# 01_JUMPER.net
KiCad netlist of a schematic drawn in Altium Designer
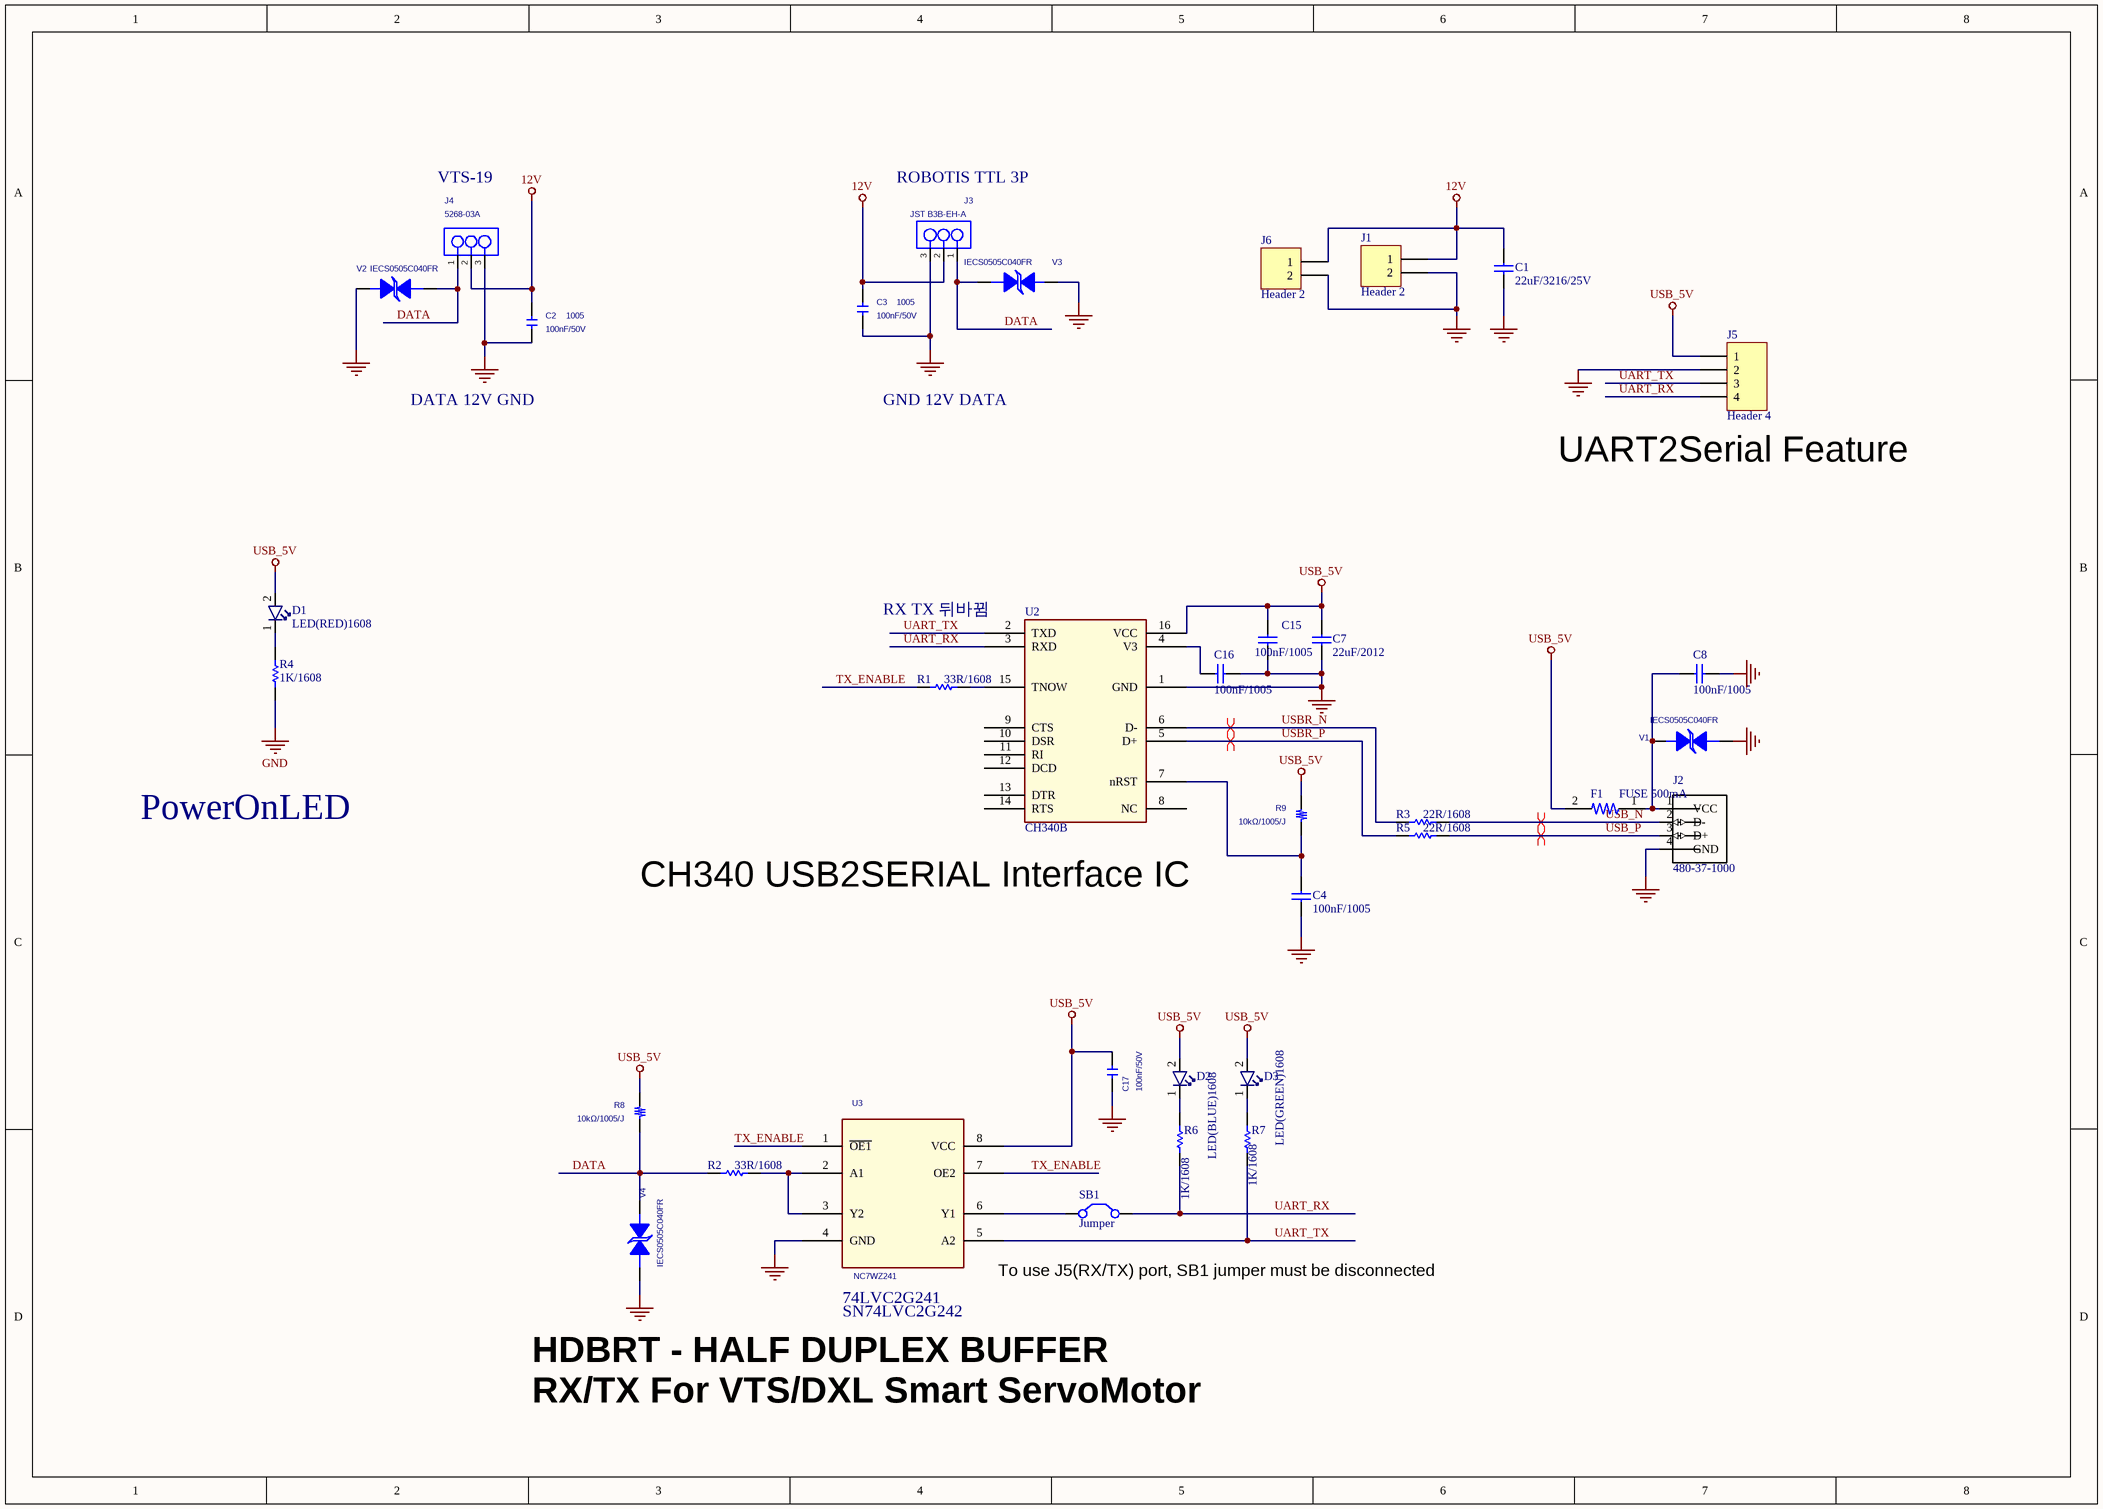
[diagram p0: 01_JUMPER.SchDoc]

(export (version "E")
  (design (tool "Eeschema 10.0.6"))
  (components
    (comp (ref "C1")
      (value "22uF/3216/25V")
      (footprint "C3216-LJS")
      (description "Capacitor, NP0, ±0.1pF")
      (libsource (lib "RLC") (part "CAP_0402"))
    )
    (comp (ref "C2")
      (value "100nF/50V")
      (footprint "CAPC1608X06L")
      (fields (field (name "SIZE") "1005") (field (name "Comment") "CAP-CHIP-1005"))
      (libsource (lib "*") (part "CAP-CHIP-1005"))
    )
    (comp (ref "C3")
      (value "100nF/50V")
      (footprint "CAPC1608X06L")
      (fields (field (name "SIZE") "1005") (field (name "Comment") "CAP-CHIP-1005"))
      (libsource (lib "*") (part "CAP-CHIP-1005"))
    )
    (comp (ref "C4")
      (value "100nF/1005")
      (footprint "CAPC1608X06L")
      (description "Capacitor, NP0, ±0.1pF")
      (libsource (lib "RLC") (part "CAP_0402"))
    )
    (comp (ref "C7")
      (value "22uF/2012")
      (footprint "CAPC2012X00L")
      (description "Capacitor, NP0, ±0.1pF")
      (libsource (lib "RLC") (part "CAP_0402"))
    )
    (comp (ref "C8")
      (value "100nF/1005")
      (footprint "CAPC1608X06L")
      (description "Capacitor, NP0, ±0.1pF")
      (libsource (lib "RLC") (part "CAP_0402"))
    )
    (comp (ref "C15")
      (value "100nF/1005")
      (footprint "CAPC1608X06L")
      (description "Capacitor, NP0, ±0.1pF")
      (libsource (lib "RLC") (part "CAP_0402"))
    )
    (comp (ref "C16")
      (value "100nF/1005")
      (footprint "CAPC1608X06L")
      (description "Capacitor, NP0, ±0.1pF")
      (libsource (lib "RLC") (part "CAP_0402"))
    )
    (comp (ref "C17")
      (value "100nF/50V")
      (footprint "CAPC1608X06L")
      (fields (field (name "Comment") "CAP-CHIP-1005"))
      (libsource (lib "*") (part "CAP-CHIP-1005"))
    )
    (comp (ref "D1")
      (value "LED(RED)1608")
      (footprint "LED_0603_G")
      (description "LED SMARTLED GREEN 570NM 0603")
      (libsource (lib "RLC") (part "D{colon}LED"))
    )
    (comp (ref "D2")
      (value "LED(BLUE)1608")
      (footprint "LED_0603_G")
      (description "LED SMARTLED GREEN 570NM 0603")
      (libsource (lib "RLC") (part "D{colon}LED"))
    )
    (comp (ref "D3")
      (value "LED(GREEN)1608")
      (footprint "LED_0603_G")
      (description "LED SMARTLED GREEN 570NM 0603")
      (libsource (lib "RLC") (part "D{colon}LED"))
    )
    (comp (ref "F1")
      (value "FUSE 500mA")
      (footprint "FUSE1812")
      (description "1206 SMT PPTC ¦ 0.50 Ih ¦ 24V")
      (fields (field (name "MP") "0ZCJ0050AF2E") (field (name "MF") "Bel Fuse"))
      (libsource (lib "VTC-1_v1.2") (part "0ZCJ0050AF2E"))
    )
    (comp (ref "J1")
      (value "Header 2")
      (footprint "HDR1X2")
      (description "Header, 2-Pin")
      (fields (field (name "PUBLISHER") "Altium Limited"))
      (libsource (lib "Miscellaneous Connectors") (part "Header 2"))
    )
    (comp (ref "J2")
      (value "480-37-1000")
      (footprint "MOLEX_480-37-1000")
      (description "USB-A _USB TYPE-A_ USB 2.0 Plug Connector 4 Position Surface Mount, Right Angle; Through Hole")
      (fields (field (name "MP") "48037-1000") (field (name "MF") "Molex"))
      (libsource (lib "Connector") (part "480-37-1000"))
    )
    (comp (ref "J3")
      (value "JST B3B-EH-A")
      (footprint "JST_B3B-EH-A")
      (libsource (lib "*") (part "5268-03A"))
    )
    (comp (ref "J4") (value "5268-03A") (footprint "5267-03") (libsource (lib "*") (part "5268-03A")))
    (comp (ref "J5")
      (value "Header 4")
      (footprint "5267-04A-2.5P")
      (description "Header, 4-Pin")
      (fields (field (name "PUBLISHER") "Altium Limited"))
      (libsource (lib "Miscellaneous Connectors") (part "Header 4"))
    )
    (comp (ref "J6")
      (value "Header 2")
      (footprint "BLOCK-5.08MMX2P_NO_SILK")
      (description "Header, 2-Pin")
      (fields (field (name "PUBLISHER") "Altium Limited"))
      (libsource (lib "Miscellaneous Connectors") (part "Header 2"))
    )
    (comp (ref "R1")
      (value "33R/1608")
      (footprint "RESC1608X06L")
      (description "Not mounted")
      (libsource (lib "RLC") (part "RES_0603"))
    )
    (comp (ref "R2")
      (value "33R/1608")
      (footprint "RESC1608X06L")
      (description "Not mounted")
      (libsource (lib "RLC") (part "RES_0603"))
    )
    (comp (ref "R3")
      (value "22R/1608")
      (footprint "RESC1608X06L")
      (description "Not mounted")
      (libsource (lib "RLC") (part "RES_0603"))
    )
    (comp (ref "R4")
      (value "1K/1608")
      (footprint "RESC1608X06L")
      (description "Not mounted")
      (libsource (lib "RLC") (part "RES_0603"))
    )
    (comp (ref "R5")
      (value "22R/1608")
      (footprint "RESC1608X06L")
      (description "Not mounted")
      (libsource (lib "RLC") (part "RES_0603"))
    )
    (comp (ref "R6")
      (value "1K/1608")
      (footprint "RESC1608X06L")
      (description "Not mounted")
      (libsource (lib "RLC") (part "RES_0603"))
    )
    (comp (ref "R7")
      (value "1K/1608")
      (footprint "RESC1608X06L")
      (description "Not mounted")
      (libsource (lib "RLC") (part "RES_0603"))
    )
    (comp (ref "R8")
      (value "10kΩ/1005/J")
      (footprint "RESC1608X06L")
      (fields (field (name "Comment") "RES-CHIP-1005"))
      (libsource (lib "*") (part "RES-CHIP-1005"))
    )
    (comp (ref "R9")
      (value "10kΩ/1005/J")
      (footprint "RESC1608X06L")
      (fields (field (name "Comment") "RES-CHIP-1005"))
      (libsource (lib "*") (part "RES-CHIP-1005"))
    )
    (comp (ref "SB1")
      (value "Jumper")
      (footprint "Solderbridge_Shorted")
      (description "Jumper Wire")
      (fields (field (name "PUBLISHER") "Altium Limited"))
      (libsource (lib "Miscellaneous Devices") (part "Jumper"))
    )
    (comp (ref "U2") (value "CH340B") (footprint "SOIC16P-50MIL") (libsource (lib "IC") (part "CH340B")))
    (comp (ref "U3")
      (value "NC7WZ241")
      (footprint "MO-187_0.5_2.0X3.1")
      (libsource (lib "*") (part "NC7WZ241"))
    )
    (comp (ref "V1")
      (value "IECS0505C040FR")
      (footprint "RESC1608X06L")
      (libsource (lib "*") (part "DIODE TVS_1"))
    )
    (comp (ref "V2")
      (value "IECS0505C040FR")
      (footprint "RESC1608X06L")
      (libsource (lib "*") (part "DIODE TVS_1"))
    )
    (comp (ref "V3")
      (value "IECS0505C040FR")
      (footprint "RESC1608X06L")
      (libsource (lib "*") (part "DIODE TVS_1"))
    )
    (comp (ref "V4")
      (value "IECS0505C040FR")
      (footprint "RESC1608X06L")
      (libsource (lib "*") (part "DIODE TVS_1"))
    )
  )
  (nets
    (net (code "1") (name "/DATA") (class "Default")
      (node (ref "J3") (pin "1") (pinfunction "1_1") (pintype "passive"))
      (node (ref "J4") (pin "1") (pinfunction "1_1") (pintype "passive"))
      (node (ref "R2") (pin "2") (pinfunction "2_2") (pintype "passive"))
      (node (ref "R8") (pin "1") (pinfunction "1_1") (pintype "passive"))
      (node (ref "V2") (pin "1") (pinfunction "ANODE_1") (pintype "passive"))
      (node (ref "V3") (pin "1") (pinfunction "ANODE_1") (pintype "passive"))
      (node (ref "V4") (pin "2") (pinfunction "CATHODE_2") (pintype "passive"))
    )
    (net (code "2") (name "/TX_ENABLE") (class "Default")
      (node (ref "R1") (pin "2") (pinfunction "2_2") (pintype "passive"))
      (node (ref "U3") (pin "1") (pinfunction "~{OE1}_1") (pintype "passive"))
      (node (ref "U3") (pin "7") (pinfunction "OE2_7") (pintype "passive"))
    )
    (net (code "3") (name "/UART_RX") (class "Default")
      (node (ref "J5") (pin "4") (pinfunction "4_4") (pintype "passive"))
      (node (ref "R6") (pin "1") (pinfunction "1_1") (pintype "passive"))
      (node (ref "SB1") (pin "2") (pinfunction "C2_2") (pintype "passive"))
      (node (ref "U2") (pin "3") (pinfunction "RXD_3") (pintype "passive"))
    )
    (net (code "4") (name "/UART_TX") (class "Default")
      (node (ref "J5") (pin "3") (pinfunction "3_3") (pintype "passive"))
      (node (ref "R7") (pin "1") (pinfunction "1_1") (pintype "passive"))
      (node (ref "U2") (pin "2") (pinfunction "TXD_2") (pintype "passive"))
      (node (ref "U3") (pin "5") (pinfunction "A2_5") (pintype "passive"))
    )
    (net (code "5") (name "/USBR_N") (class "Default")
      (node (ref "R3") (pin "2") (pinfunction "2_2") (pintype "passive"))
      (node (ref "U2") (pin "6") (pinfunction "D-_6") (pintype "passive"))
    )
    (net (code "6") (name "/USBR_P") (class "Default")
      (node (ref "R5") (pin "2") (pinfunction "2_2") (pintype "passive"))
      (node (ref "U2") (pin "5") (pinfunction "D+_5") (pintype "passive"))
    )
    (net (code "7") (name "/USB_N") (class "Default")
      (node (ref "J2") (pin "2") (pinfunction "D-_2") (pintype "bidirectional"))
      (node (ref "R3") (pin "1") (pinfunction "1_1") (pintype "passive"))
    )
    (net (code "8") (name "/USB_P") (class "Default")
      (node (ref "J2") (pin "3") (pinfunction "D+_3") (pintype "bidirectional"))
      (node (ref "R5") (pin "1") (pinfunction "1_1") (pintype "passive"))
    )
    (net (code "9") (name "12V") (class "Default")
      (node (ref "C1") (pin "1") (pinfunction "1_1") (pintype "passive"))
      (node (ref "C2") (pin "2") (pinfunction "2_2") (pintype "passive"))
      (node (ref "C3") (pin "2") (pinfunction "2_2") (pintype "passive"))
      (node (ref "J1") (pin "1") (pinfunction "1_1") (pintype "passive"))
      (node (ref "J3") (pin "2") (pinfunction "2_2") (pintype "passive"))
      (node (ref "J4") (pin "2") (pinfunction "2_2") (pintype "passive"))
      (node (ref "J6") (pin "1") (pinfunction "1_1") (pintype "passive"))
    )
    (net (code "10") (name "GND") (class "Default")
      (node (ref "C1") (pin "2") (pinfunction "2_2") (pintype "passive"))
      (node (ref "C15") (pin "2") (pinfunction "2_2") (pintype "passive"))
      (node (ref "C16") (pin "2") (pinfunction "2_2") (pintype "passive"))
      (node (ref "C17") (pin "1") (pinfunction "1_1") (pintype "passive"))
      (node (ref "C2") (pin "1") (pinfunction "1_1") (pintype "passive"))
      (node (ref "C3") (pin "1") (pinfunction "1_1") (pintype "passive"))
      (node (ref "C4") (pin "1") (pinfunction "1_1") (pintype "passive"))
      (node (ref "C7") (pin "2") (pinfunction "2_2") (pintype "passive"))
      (node (ref "C8") (pin "2") (pinfunction "2_2") (pintype "passive"))
      (node (ref "J1") (pin "2") (pinfunction "2_2") (pintype "passive"))
      (node (ref "J2") (pin "4") (pinfunction "GND_4") (pintype "power_in"))
      (node (ref "J3") (pin "3") (pinfunction "3_3") (pintype "passive"))
      (node (ref "J4") (pin "3") (pinfunction "3_3") (pintype "passive"))
      (node (ref "J5") (pin "2") (pinfunction "2_2") (pintype "passive"))
      (node (ref "J6") (pin "2") (pinfunction "2_2") (pintype "passive"))
      (node (ref "R4") (pin "1") (pinfunction "1_1") (pintype "passive"))
      (node (ref "U2") (pin "1") (pinfunction "GND_1") (pintype "power_in"))
      (node (ref "U3") (pin "4") (pinfunction "GND_4") (pintype "passive"))
      (node (ref "V1") (pin "1") (pinfunction "ANODE_1") (pintype "passive"))
      (node (ref "V2") (pin "2") (pinfunction "CATHODE_2") (pintype "passive"))
      (node (ref "V3") (pin "2") (pinfunction "CATHODE_2") (pintype "passive"))
      (node (ref "V4") (pin "1") (pinfunction "ANODE_1") (pintype "passive"))
    )
    (net (code "11") (name "Net-(D1-C)") (class "Default")
      (node (ref "D1") (pin "1") (pinfunction "C_1") (pintype "passive"))
      (node (ref "R4") (pin "2") (pinfunction "2_2") (pintype "passive"))
    )
    (net (code "12") (name "Net-(D2-C)") (class "Default")
      (node (ref "D2") (pin "1") (pinfunction "C_1") (pintype "passive"))
      (node (ref "R6") (pin "2") (pinfunction "2_2") (pintype "passive"))
    )
    (net (code "13") (name "Net-(D3-C)") (class "Default")
      (node (ref "D3") (pin "1") (pinfunction "C_1") (pintype "passive"))
      (node (ref "R7") (pin "2") (pinfunction "2_2") (pintype "passive"))
    )
    (net (code "14") (name "Net-(J2-VCC)") (class "Default")
      (node (ref "C8") (pin "1") (pinfunction "1_1") (pintype "passive"))
      (node (ref "F1") (pin "1") (pinfunction "1_1") (pintype "passive"))
      (node (ref "J2") (pin "1") (pinfunction "VCC_1") (pintype "power_in"))
      (node (ref "V1") (pin "2") (pinfunction "CATHODE_2") (pintype "passive"))
    )
    (net (code "15") (name "Net-(SB1-C1)") (class "Default")
      (node (ref "SB1") (pin "1") (pinfunction "C1_1") (pintype "passive"))
      (node (ref "U3") (pin "6") (pinfunction "Y1_6") (pintype "passive"))
    )
    (net (code "16") (name "Net-(U2-TNOW)") (class "Default")
      (node (ref "R1") (pin "1") (pinfunction "1_1") (pintype "passive"))
      (node (ref "U2") (pin "15") (pinfunction "TNOW_15") (pintype "power_in"))
    )
    (net (code "17") (name "Net-(U2-V3)") (class "Default")
      (node (ref "C16") (pin "1") (pinfunction "1_1") (pintype "passive"))
      (node (ref "U2") (pin "4") (pinfunction "V3_4") (pintype "passive"))
    )
    (net (code "18") (name "Net-(U2-nRST)") (class "Default")
      (node (ref "C4") (pin "2") (pinfunction "2_2") (pintype "passive"))
      (node (ref "R9") (pin "1") (pinfunction "1_1") (pintype "passive"))
      (node (ref "U2") (pin "7") (pinfunction "nRST_7") (pintype "passive"))
    )
    (net (code "19") (name "Net-(U3-A1)") (class "Default")
      (node (ref "R2") (pin "1") (pinfunction "1_1") (pintype "passive"))
      (node (ref "U3") (pin "2") (pinfunction "A1_2") (pintype "passive"))
      (node (ref "U3") (pin "3") (pinfunction "Y2_3") (pintype "passive"))
    )
    (net (code "20") (name "USB_5V") (class "Default")
      (node (ref "C15") (pin "1") (pinfunction "1_1") (pintype "passive"))
      (node (ref "C17") (pin "2") (pinfunction "2_2") (pintype "passive"))
      (node (ref "C7") (pin "1") (pinfunction "1_1") (pintype "passive"))
      (node (ref "D1") (pin "2") (pinfunction "A_2") (pintype "passive"))
      (node (ref "D2") (pin "2") (pinfunction "A_2") (pintype "passive"))
      (node (ref "D3") (pin "2") (pinfunction "A_2") (pintype "passive"))
      (node (ref "F1") (pin "2") (pinfunction "2_2") (pintype "passive"))
      (node (ref "J5") (pin "1") (pinfunction "1_1") (pintype "passive"))
      (node (ref "R8") (pin "2") (pinfunction "2_2") (pintype "passive"))
      (node (ref "R9") (pin "2") (pinfunction "2_2") (pintype "passive"))
      (node (ref "U2") (pin "16") (pinfunction "VCC_16") (pintype "power_in"))
      (node (ref "U3") (pin "8") (pinfunction "VCC_8") (pintype "passive"))
    )
    (net (code "21") (name "unconnected-(U2-CTS-Pad9)") (class "Default")
      (node (ref "U2") (pin "9") (pinfunction "CTS_9") (pintype "passive"))
    )
    (net (code "22") (name "unconnected-(U2-DCD-Pad12)") (class "Default")
      (node (ref "U2") (pin "12") (pinfunction "DCD_12") (pintype "passive"))
    )
    (net (code "23") (name "unconnected-(U2-DSR-Pad10)") (class "Default")
      (node (ref "U2") (pin "10") (pinfunction "DSR_10") (pintype "passive"))
    )
    (net (code "24") (name "unconnected-(U2-DTR-Pad13)") (class "Default")
      (node (ref "U2") (pin "13") (pinfunction "DTR_13") (pintype "passive"))
    )
    (net (code "25") (name "unconnected-(U2-NC-Pad8)") (class "Default")
      (node (ref "U2") (pin "8") (pinfunction "NC_8") (pintype "passive"))
    )
    (net (code "26") (name "unconnected-(U2-RI-Pad11)") (class "Default")
      (node (ref "U2") (pin "11") (pinfunction "RI_11") (pintype "passive"))
    )
    (net (code "27") (name "unconnected-(U2-RTS-Pad14)") (class "Default")
      (node (ref "U2") (pin "14") (pinfunction "RTS_14") (pintype "passive"))
    )
  )
)
